# NST_output_read.net
KiCad netlist of a schematic drawn in EAGLE
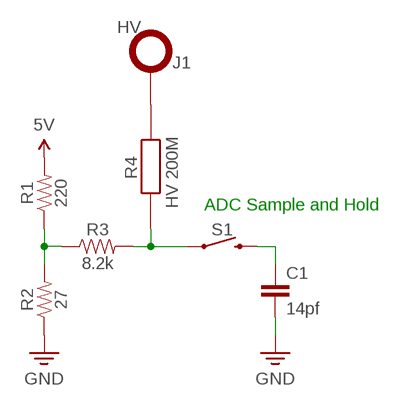
[diagram p0: schematic, sheet 1]

(export (version "E")
  (design (tool "Eeschema 10.0.6"))
  (components
    (comp (ref "C1")
      (value "14pf")
      (footprint "eagle-import:CAP-PTH-10MM")
      (libsource (lib "eagle-import") (part "10NF-PTH-10MM-10000V-1-%"))
    )
    (comp (ref "J1")
      (value "HV")
      (footprint "eagle-import:LUG_SQUARE_M6")
      (libsource (lib "eagle-import") (part "TERMINAL_M6"))
    )
    (comp (ref "R1")
      (value "220")
      (footprint "eagle-import:AXIAL-0.3")
      (libsource (lib "eagle-import") (part "15KOHM-HORIZ-1/4W-5%"))
    )
    (comp (ref "R2")
      (value "27")
      (footprint "eagle-import:AXIAL-0.3")
      (libsource (lib "eagle-import") (part "15KOHM-HORIZ-1/4W-5%"))
    )
    (comp (ref "R3")
      (value "8.2k")
      (footprint "eagle-import:AXIAL-0.3")
      (libsource (lib "eagle-import") (part "15KOHM-HORIZ-1/4W-5%"))
    )
    (comp (ref "R4")
      (value "HV 200M")
      (footprint "eagle-import:SM108031007FE")
      (fields
        (field (name "MANUFACTURER_PART_NUMBER") "SM108031005FE")
        (field (name "RS_PART_NUMBER") "8927338")
      )
      (libsource (lib "eagle-import") (part "SM108031005FE"))
    )
    (comp (ref "S1")
      (value "MOMENTARY-SWITCH-SPST-PTH-6.0MM")
      (footprint "eagle-import:TACTILE_SWITCH_PTH_6.0MM")
      (libsource (lib "eagle-import") (part "MOMENTARY-SWITCH-SPST-PTH-6.0MM"))
    )
  )
  (nets
    (net (code "1") (name "5V") (class "Default")
      (node (ref "R1") (pin "P$2") (pinfunction "2_P$2") (pintype "passive"))
    )
    (net (code "2") (name "GND") (class "Default")
      (node (ref "C1") (pin "2") (pinfunction "2_2") (pintype "passive"))
      (node (ref "R2") (pin "P$1") (pinfunction "1_P$1") (pintype "passive"))
    )
    (net (code "3") (name "Net-(J1-PadP$1)") (class "Default")
      (node (ref "J1") (pin "P$1") (pinfunction "P$1_P$1") (pintype "passive"))
      (node (ref "R4") (pin "2") (pinfunction "2_2") (pintype "bidirectional"))
    )
    (net (code "4") (name "Net-(R1-1)") (class "Default")
      (node (ref "R1") (pin "P$1") (pinfunction "1_P$1") (pintype "passive"))
      (node (ref "R2") (pin "P$2") (pinfunction "2_P$2") (pintype "passive"))
      (node (ref "R3") (pin "P$1") (pinfunction "1_P$1") (pintype "passive"))
    )
    (net (code "5") (name "Net-(R3-2)") (class "Default")
      (node (ref "R3") (pin "P$2") (pinfunction "2_P$2") (pintype "passive"))
      (node (ref "R4") (pin "1") (pinfunction "1_1") (pintype "bidirectional"))
      (node (ref "S1") (pin "1") (pinfunction "1_1") (pintype "passive"))
    )
    (net (code "6") (name "Net-(S1-2)") (class "Default")
      (node (ref "C1") (pin "1") (pinfunction "1_1") (pintype "passive"))
      (node (ref "S1") (pin "3") (pinfunction "2_3") (pintype "passive"))
    )
  )
)
